# ArmazEthernet_-_Rev_A3.net
KiCad netlist of a schematic drawn in EAGLE
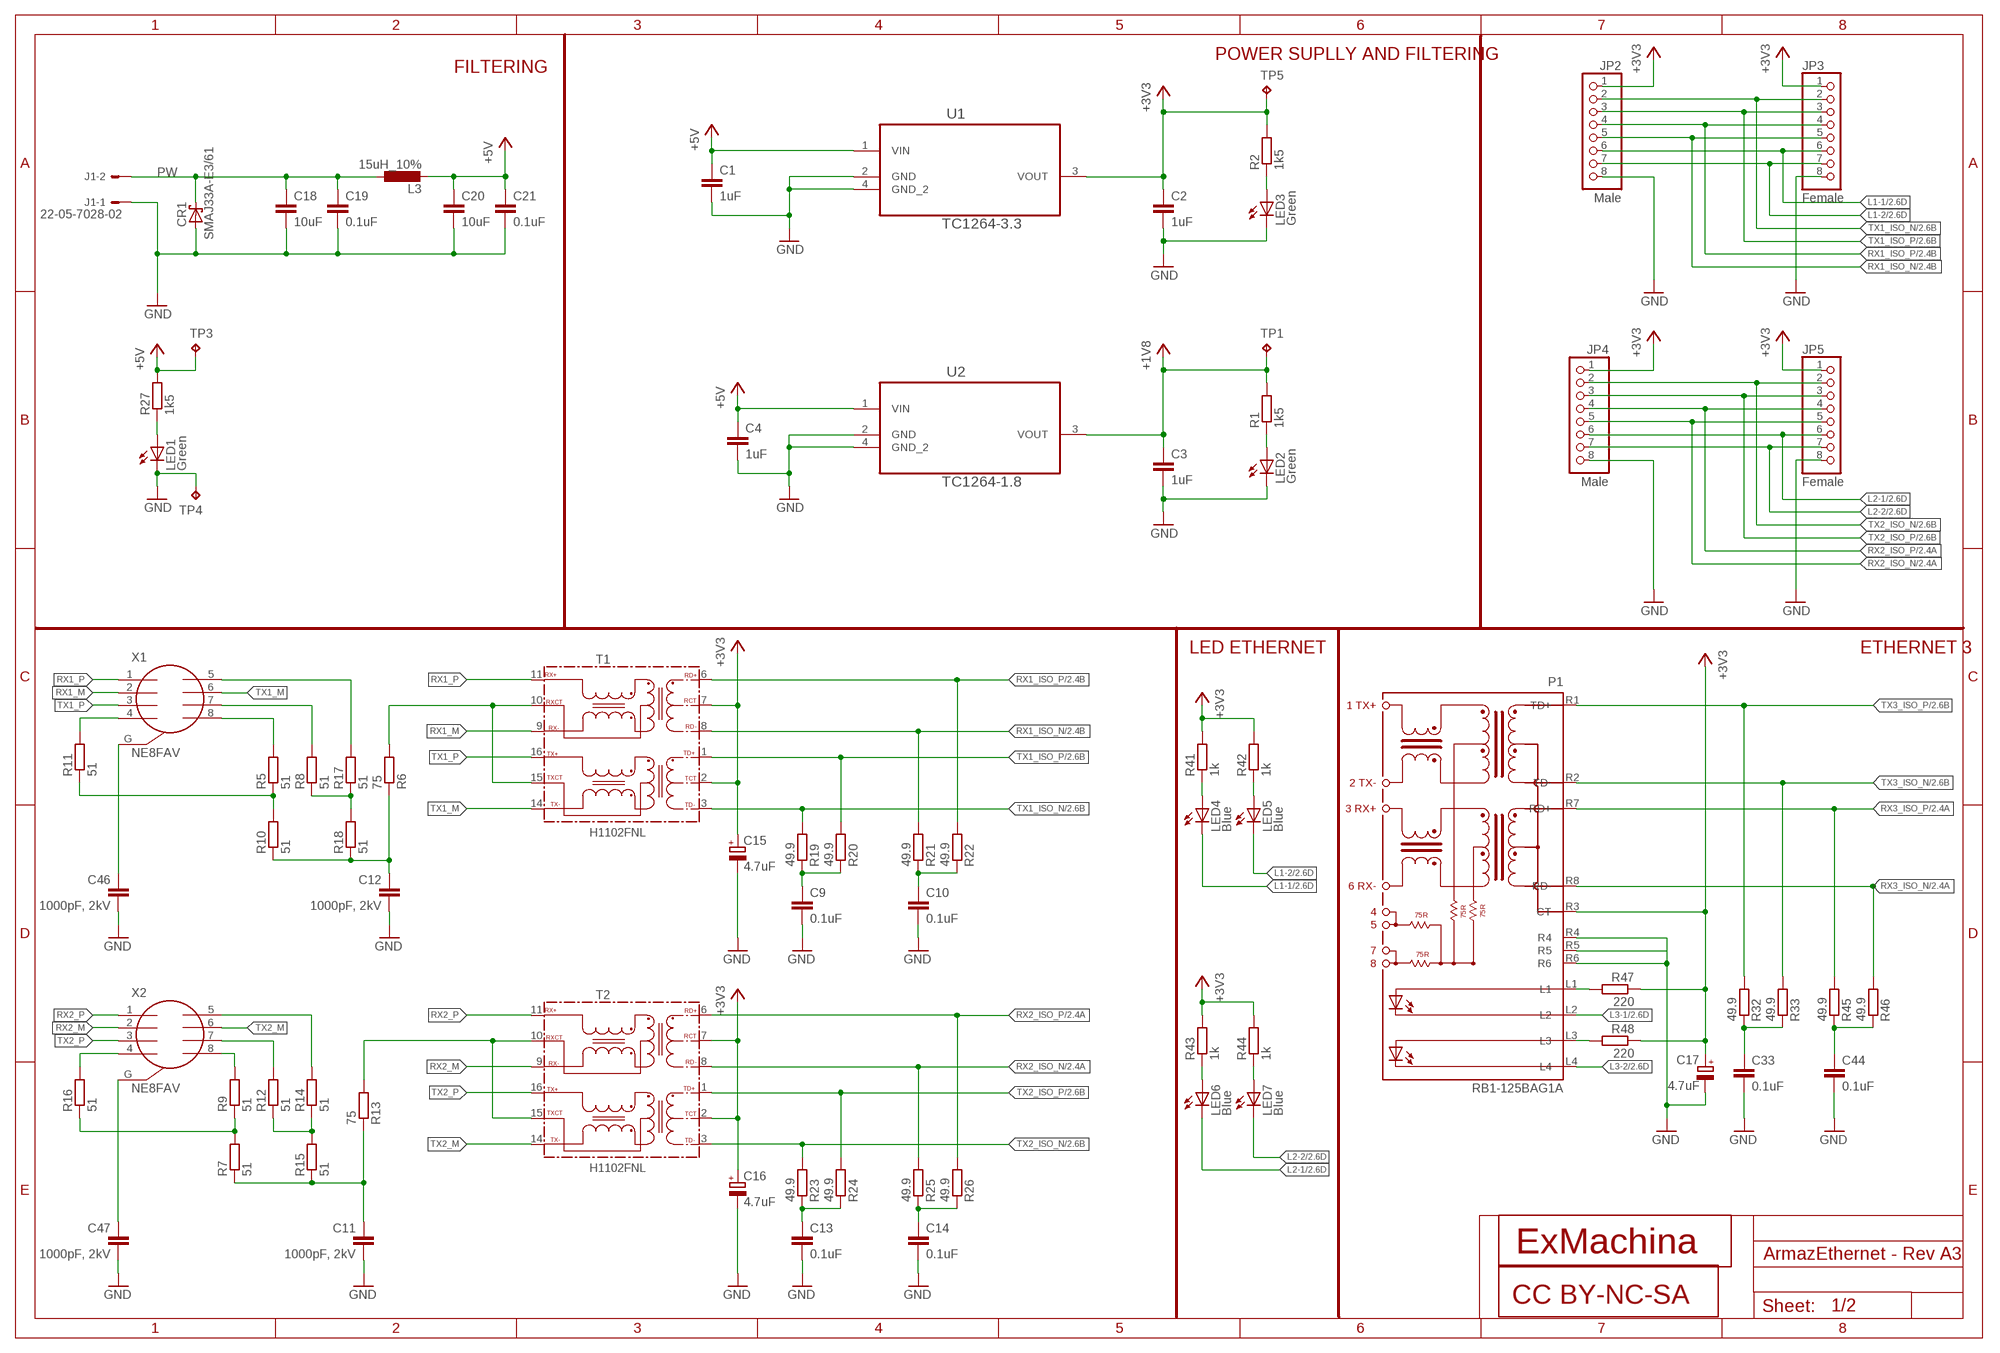
[diagram p0: schematic, sheet 1]
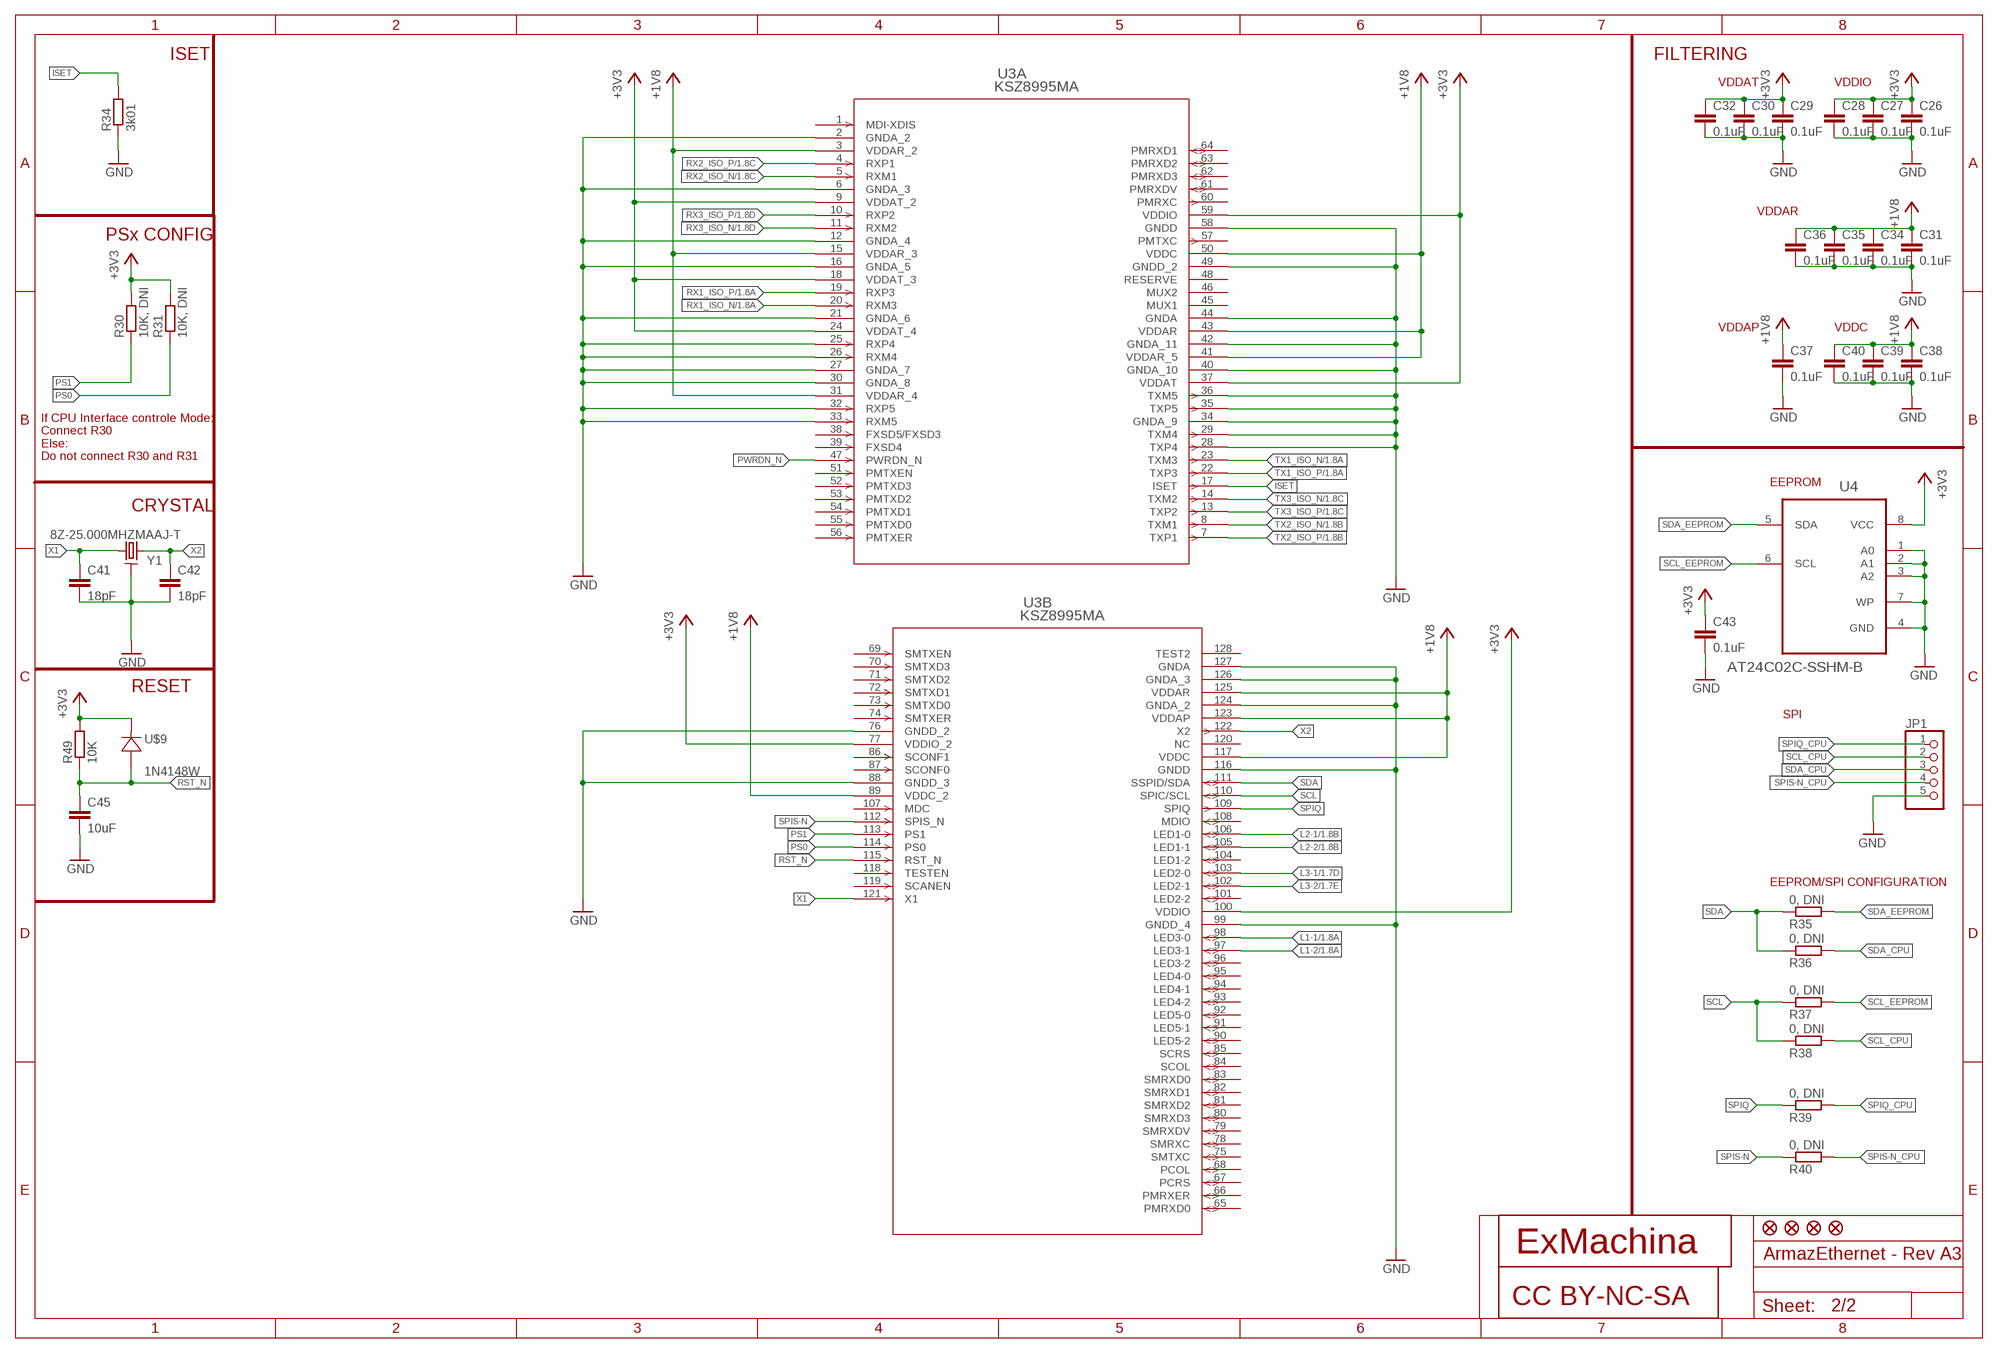
[diagram p1: schematic, sheet 2]

(export (version "E")
  (design (tool "Eeschema 10.0.6"))
  (components
    (comp (ref "C26")
      (value "0.1uF")
      (footprint "eagle-import:C0603")
      (fields (field (name "MF") "MULTICOMP") (field (name "MPN") "MC0603B104K250CT"))
      (libsource (lib "eagle-import") (part "C-EUC0603"))
    )
    (comp (ref "C27")
      (value "0.1uF")
      (footprint "eagle-import:C0603")
      (fields (field (name "MF") "MULTICOMP") (field (name "MPN") "MC0603B104K250CT"))
      (libsource (lib "eagle-import") (part "C-EUC0603"))
    )
    (comp (ref "C28")
      (value "0.1uF")
      (footprint "eagle-import:C0603")
      (fields (field (name "MF") "MULTICOMP") (field (name "MPN") "MC0603B104K250CT"))
      (libsource (lib "eagle-import") (part "C-EUC0603"))
    )
    (comp (ref "C29")
      (value "0.1uF")
      (footprint "eagle-import:C0603")
      (fields (field (name "MF") "MULTICOMP") (field (name "MPN") "MC0603B104K250CT"))
      (libsource (lib "eagle-import") (part "C-EUC0603"))
    )
    (comp (ref "C30")
      (value "0.1uF")
      (footprint "eagle-import:C0603")
      (fields (field (name "MF") "MULTICOMP") (field (name "MPN") "MC0603B104K250CT"))
      (libsource (lib "eagle-import") (part "C-EUC0603"))
    )
    (comp (ref "C31")
      (value "0.1uF")
      (footprint "eagle-import:C0603")
      (fields (field (name "MF") "MULTICOMP") (field (name "MPN") "MC0603B104K250CT"))
      (libsource (lib "eagle-import") (part "C-EUC0603"))
    )
    (comp (ref "C32")
      (value "0.1uF")
      (footprint "eagle-import:C0603")
      (fields (field (name "MF") "MULTICOMP") (field (name "MPN") "MC0603B104K250CT"))
      (libsource (lib "eagle-import") (part "C-EUC0603"))
    )
    (comp (ref "C34")
      (value "0.1uF")
      (footprint "eagle-import:C0603")
      (fields (field (name "MF") "MULTICOMP") (field (name "MPN") "MC0603B104K250CT"))
      (libsource (lib "eagle-import") (part "C-EUC0603"))
    )
    (comp (ref "C35")
      (value "0.1uF")
      (footprint "eagle-import:C0603")
      (fields (field (name "MF") "MULTICOMP") (field (name "MPN") "MC0603B104K250CT"))
      (libsource (lib "eagle-import") (part "C-EUC0603"))
    )
    (comp (ref "C36")
      (value "0.1uF")
      (footprint "eagle-import:C0603")
      (fields (field (name "MF") "MULTICOMP") (field (name "MPN") "MC0603B104K250CT"))
      (libsource (lib "eagle-import") (part "C-EUC0603"))
    )
    (comp (ref "C37")
      (value "0.1uF")
      (footprint "eagle-import:C0603")
      (fields (field (name "MF") "MULTICOMP") (field (name "MPN") "MC0603B104K250CT"))
      (libsource (lib "eagle-import") (part "C-EUC0603"))
    )
    (comp (ref "C38")
      (value "0.1uF")
      (footprint "eagle-import:C0603")
      (fields (field (name "MF") "MULTICOMP") (field (name "MPN") "MC0603B104K250CT"))
      (libsource (lib "eagle-import") (part "C-EUC0603"))
    )
    (comp (ref "C39")
      (value "0.1uF")
      (footprint "eagle-import:C0603")
      (fields (field (name "MF") "MULTICOMP") (field (name "MPN") "MC0603B104K250CT"))
      (libsource (lib "eagle-import") (part "C-EUC0603"))
    )
    (comp (ref "C40")
      (value "0.1uF")
      (footprint "eagle-import:C0603")
      (fields (field (name "MF") "MULTICOMP") (field (name "MPN") "MC0603B104K250CT"))
      (libsource (lib "eagle-import") (part "C-EUC0603"))
    )
    (comp (ref "C41")
      (value "18pF")
      (footprint "eagle-import:C0603")
      (fields (field (name "MF") "MULTICOMP") (field (name "MPN") "MC0603B183K160CT"))
      (libsource (lib "eagle-import") (part "C-EUC0603"))
    )
    (comp (ref "C42")
      (value "18pF")
      (footprint "eagle-import:C0603")
      (fields (field (name "MF") "MULTICOMP") (field (name "MPN") "MC0603B183K160CT"))
      (libsource (lib "eagle-import") (part "C-EUC0603"))
    )
    (comp (ref "C43")
      (value "0.1uF")
      (footprint "eagle-import:C0603")
      (fields (field (name "MF") "MULTICOMP") (field (name "MPN") "MC0603B104K250CT"))
      (libsource (lib "eagle-import") (part "C-EUC0603"))
    )
    (comp (ref "C45")
      (value "10uF")
      (footprint "eagle-import:C0603")
      (fields (field (name "MF") "MURATA") (field (name "MPN") "GRM32DR71C106KA01L"))
      (libsource (lib "eagle-import") (part "C-EUC0603"))
    )
    (comp (ref "JP1")
      (value "PINHD-1X5")
      (footprint "eagle-import:1X05")
      (libsource (lib "eagle-import") (part "PINHD-1X5"))
    )
    (comp (ref "JP7")
      (value "FIDUCIAL1X2")
      (footprint "eagle-import:FIDUCIAL-1X2")
      (libsource (lib "eagle-import") (part "FIDUCIAL1X2"))
    )
    (comp (ref "JP8")
      (value "FIDUCIAL1X2")
      (footprint "eagle-import:FIDUCIAL-1X2")
      (libsource (lib "eagle-import") (part "FIDUCIAL1X2"))
    )
    (comp (ref "JP9")
      (value "FIDUCIAL1X2")
      (footprint "eagle-import:FIDUCIAL-1X2")
      (libsource (lib "eagle-import") (part "FIDUCIAL1X2"))
    )
    (comp (ref "JP10")
      (value "FIDUCIAL1X2")
      (footprint "eagle-import:FIDUCIAL-1X2")
      (libsource (lib "eagle-import") (part "FIDUCIAL1X2"))
    )
    (comp (ref "R30")
      (value "10K, DNI")
      (footprint "eagle-import:R0603")
      (libsource (lib "eagle-import") (part "R-EU_R0603"))
    )
    (comp (ref "R31")
      (value "10K, DNI")
      (footprint "eagle-import:R0603")
      (libsource (lib "eagle-import") (part "R-EU_R0603"))
    )
    (comp (ref "R34")
      (value "3k01")
      (footprint "eagle-import:R0603")
      (fields (field (name "MF") "MULTICOMP") (field (name "MPN") "MCMR06X3001FTL"))
      (libsource (lib "eagle-import") (part "R-EU_R0603"))
    )
    (comp (ref "R35")
      (value "0, DNI")
      (footprint "eagle-import:R0603")
      (libsource (lib "eagle-import") (part "R-EU_R0603"))
    )
    (comp (ref "R36")
      (value "0, DNI")
      (footprint "eagle-import:R0603")
      (libsource (lib "eagle-import") (part "R-EU_R0603"))
    )
    (comp (ref "R37")
      (value "0, DNI")
      (footprint "eagle-import:R0603")
      (libsource (lib "eagle-import") (part "R-EU_R0603"))
    )
    (comp (ref "R38")
      (value "0, DNI")
      (footprint "eagle-import:R0603")
      (libsource (lib "eagle-import") (part "R-EU_R0603"))
    )
    (comp (ref "R39")
      (value "0, DNI")
      (footprint "eagle-import:R0603")
      (libsource (lib "eagle-import") (part "R-EU_R0603"))
    )
    (comp (ref "R40")
      (value "0, DNI")
      (footprint "eagle-import:R0603")
      (libsource (lib "eagle-import") (part "R-EU_R0603"))
    )
    (comp (ref "R49")
      (value "10K")
      (footprint "eagle-import:R0603")
      (fields (field (name "MF") "MULTICOMP") (field (name "MPN") "MCMR06X1002FTL"))
      (libsource (lib "eagle-import") (part "R-EU_R0603"))
    )
    (comp (ref "U$7")
      (value "CC-BY-NC-SA")
      (footprint "eagle-import:CC-BY-NC-SA")
      (libsource (lib "eagle-import") (part "CC-BY-NC-SA"))
    )
    (comp (ref "U$8")
      (value "EXMACHINA-LOGO-NAME")
      (footprint "eagle-import:EXM-LOGO-BASELINE")
      (libsource (lib "eagle-import") (part "EXMACHINA-LOGO-NAME"))
    )
    (comp (ref "U$9")
      (value "1N4148W")
      (footprint "eagle-import:SOD-123_MINI-SMA")
      (libsource (lib "eagle-import") (part "1N4148W"))
    )
    (comp (ref "U3")
      (value "KSZ8995MA")
      (footprint "eagle-import:PQFP-128_MQL")
      (fields
        (field (name "MANUFACTURER_PART_NUMBER") "ksz8995ma")
        (field (name "MF") "MICROCHIP")
        (field (name "MPN") "KSZ8995MA")
        (field (name "OC_FARNELL") "2509844")
        (field (name "OC_NEWARK") "70Y9044")
        (field (name "COPYRIGHT") "Copyright (C) 2015 Accelerated Designs. All rights reserved")
      )
      (libsource (lib "eagle-import") (part "KSZ8995MA"))
    )
    (comp (ref "U4")
      (value "AT24C02C-SSHM-B")
      (footprint "eagle-import:SOIC127P600X175-8N")
      (fields (field (name "MF") "ATMEL") (field (name "OC_FARNELL") "1971995"))
      (libsource (lib "eagle-import") (part "AT24C02C-SSHM-B"))
    )
    (comp (ref "Y1")
      (value "8Z-25.000MHZMAAJ-T")
      (footprint "eagle-import:SMD2.5X2")
      (fields (field (name "MF") "TXC") (field (name "MPN") "8Z-25.000MAAJ-T"))
      (libsource (lib "eagle-import") (part "8Z-25.000MHZMAAJ-T"))
    )
    (comp (ref "C1")
      (value "1uF")
      (footprint "eagle-import:C0603")
      (libsource (lib "eagle-import") (part "C-EUC0603"))
    )
    (comp (ref "C2")
      (value "1uF")
      (footprint "eagle-import:C0603")
      (libsource (lib "eagle-import") (part "C-EUC0603"))
    )
    (comp (ref "C3")
      (value "1uF")
      (footprint "eagle-import:C0603")
      (libsource (lib "eagle-import") (part "C-EUC0603"))
    )
    (comp (ref "C4")
      (value "1uF")
      (footprint "eagle-import:C0603")
      (libsource (lib "eagle-import") (part "C-EUC0603"))
    )
    (comp (ref "C9")
      (value "0.1uF")
      (footprint "eagle-import:C0603")
      (fields (field (name "MF") "MULTICOMP") (field (name "MPN") "MC0603B104K250CT"))
      (libsource (lib "eagle-import") (part "C-EUC0603"))
    )
    (comp (ref "C10")
      (value "0.1uF")
      (footprint "eagle-import:C0603")
      (fields (field (name "MF") "MULTICOMP") (field (name "MPN") "MC0603B104K250CT"))
      (libsource (lib "eagle-import") (part "C-EUC0603"))
    )
    (comp (ref "C11")
      (value "1000pF, 2kV")
      (footprint "eagle-import:C1206")
      (libsource (lib "eagle-import") (part "C-EUC1206"))
    )
    (comp (ref "C12")
      (value "1000pF, 2kV")
      (footprint "eagle-import:C1206")
      (libsource (lib "eagle-import") (part "C-EUC1206"))
    )
    (comp (ref "C13")
      (value "0.1uF")
      (footprint "eagle-import:C0603")
      (fields (field (name "MF") "MULTICOMP") (field (name "MPN") "MC0603B104K250CT"))
      (libsource (lib "eagle-import") (part "C-EUC0603"))
    )
    (comp (ref "C14")
      (value "0.1uF")
      (footprint "eagle-import:C0603")
      (fields (field (name "MF") "MULTICOMP") (field (name "MPN") "MC0603B104K250CT"))
      (libsource (lib "eagle-import") (part "C-EUC0603"))
    )
    (comp (ref "C15")
      (value "4.7uF")
      (footprint "eagle-import:CT3216")
      (libsource (lib "eagle-import") (part "CPOL-EUCT3216"))
    )
    (comp (ref "C16")
      (value "4.7uF")
      (footprint "eagle-import:CT3216")
      (libsource (lib "eagle-import") (part "CPOL-EUCT3216"))
    )
    (comp (ref "C17")
      (value "4.7uF")
      (footprint "eagle-import:CT3216")
      (libsource (lib "eagle-import") (part "CPOL-EUCT3216"))
    )
    (comp (ref "C18")
      (value "10uF")
      (footprint "eagle-import:C0603")
      (fields (field (name "MF") "MURATA") (field (name "MPN") "GRM32DR71C106KA01L"))
      (libsource (lib "eagle-import") (part "C-EUC0603"))
    )
    (comp (ref "C19")
      (value "0.1uF")
      (footprint "eagle-import:C0603")
      (fields (field (name "MF") "MULTICOMP") (field (name "MPN") "MC0603B104K250CT"))
      (libsource (lib "eagle-import") (part "C-EUC0603"))
    )
    (comp (ref "C20")
      (value "10uF")
      (footprint "eagle-import:C0603")
      (fields (field (name "MF") "MURATA") (field (name "MPN") "GRM32DR71C106KA01L"))
      (libsource (lib "eagle-import") (part "C-EUC0603"))
    )
    (comp (ref "C21")
      (value "0.1uF")
      (footprint "eagle-import:C0603")
      (fields (field (name "MF") "MULTICOMP") (field (name "MPN") "MC0603B104K250CT"))
      (libsource (lib "eagle-import") (part "C-EUC0603"))
    )
    (comp (ref "C33")
      (value "0.1uF")
      (footprint "eagle-import:C0603")
      (fields (field (name "MF") "MULTICOMP") (field (name "MPN") "MC0603B104K250CT"))
      (libsource (lib "eagle-import") (part "C-EUC0603"))
    )
    (comp (ref "C44")
      (value "0.1uF")
      (footprint "eagle-import:C0603")
      (fields (field (name "MF") "MULTICOMP") (field (name "MPN") "MC0603B104K250CT"))
      (libsource (lib "eagle-import") (part "C-EUC0603"))
    )
    (comp (ref "C46")
      (value "1000pF, 2kV")
      (footprint "eagle-import:C1206")
      (libsource (lib "eagle-import") (part "C-EUC1206"))
    )
    (comp (ref "C47")
      (value "1000pF, 2kV")
      (footprint "eagle-import:C1206")
      (libsource (lib "eagle-import") (part "C-EUC1206"))
    )
    (comp (ref "CR1")
      (value "SMAJ33A-E3/61")
      (footprint "eagle-import:DIODE_DO-214AC")
      (fields
        (field (name "RSPARTNUMBER") "7103462")
        (field (name "MF") "VISHAY")
        (field (name "MPN") "SMAJ33A-E3/5A")
        (field (name "COPYRIGHT") "Copyright (C) 2015 Accelerated Designs. All rights reserved")
      )
      (libsource (lib "eagle-import") (part "SMAJ33A-E3/61"))
    )
    (comp (ref "J1")
      (value "22-05-7028-02")
      (footprint "eagle-import:7395-02")
      (fields
        (field (name "MF") "MOLEX")
        (field (name "MPN") "22-05-7028")
        (field (name "OC_NEWARK") "25M1728")
      )
      (libsource (lib "eagle-import") (part "22-?-0205-7028"))
    )
    (comp (ref "JP2")
      (value "Male")
      (footprint "eagle-import:1X08")
      (fields (field (name "MF") "SAMTEC") (field (name "MPN") "TSW-108-15-T-S"))
      (libsource (lib "eagle-import") (part "PINHD-1X8"))
    )
    (comp (ref "JP3")
      (value "Female")
      (footprint "eagle-import:1X08")
      (fields (field (name "MF") "SAMTEC") (field (name "MPN") "SLW-108-01-T-S"))
      (libsource (lib "eagle-import") (part "PINHD-1X8"))
    )
    (comp (ref "JP4")
      (value "Male")
      (footprint "eagle-import:1X08")
      (fields (field (name "MF") "SAMTEC") (field (name "MPN") "TSW-108-15-T-S"))
      (libsource (lib "eagle-import") (part "PINHD-1X8"))
    )
    (comp (ref "JP5")
      (value "Female")
      (footprint "eagle-import:1X08")
      (fields (field (name "MF") "SAMTEC") (field (name "MPN") "SLW-108-01-T-S"))
      (libsource (lib "eagle-import") (part "PINHD-1X8"))
    )
    (comp (ref "L3")
      (value "15uH_10%")
      (footprint "eagle-import:L4532M")
      (libsource (lib "eagle-import") (part "L-EUL4532C"))
    )
    (comp (ref "LED1")
      (value "Green")
      (footprint "eagle-import:CHIP-LED0603")
      (fields (field (name "MF") "MULTICOMP") (field (name "MPN") "OVS-0604"))
      (libsource (lib "eagle-import") (part "LEDCHIP-LED0603"))
    )
    (comp (ref "LED2")
      (value "Green")
      (footprint "eagle-import:CHIP-LED0603")
      (fields (field (name "MF") "MULTICOMP") (field (name "MPN") "OVS-0604"))
      (libsource (lib "eagle-import") (part "LEDCHIP-LED0603"))
    )
    (comp (ref "LED3")
      (value "Green")
      (footprint "eagle-import:CHIP-LED0603")
      (fields (field (name "MF") "MULTICOMP") (field (name "MPN") "OVS-0604"))
      (libsource (lib "eagle-import") (part "LEDCHIP-LED0603"))
    )
    (comp (ref "LED4")
      (value "Blue")
      (footprint "eagle-import:CHIP-LED0603")
      (fields (field (name "MF") "MULTICOMP") (field (name "MPN") "OVS-0603"))
      (libsource (lib "eagle-import") (part "LEDCHIP-LED0603"))
    )
    (comp (ref "LED5")
      (value "Blue")
      (footprint "eagle-import:CHIP-LED0603")
      (fields (field (name "MF") "MULTICOMP") (field (name "MPN") "OVS-0603"))
      (libsource (lib "eagle-import") (part "LEDCHIP-LED0603"))
    )
    (comp (ref "LED6")
      (value "Blue")
      (footprint "eagle-import:CHIP-LED0603")
      (fields (field (name "MF") "MULTICOMP") (field (name "MPN") "OVS-0603"))
      (libsource (lib "eagle-import") (part "LEDCHIP-LED0603"))
    )
    (comp (ref "LED7")
      (value "Blue")
      (footprint "eagle-import:CHIP-LED0603")
      (fields (field (name "MF") "MULTICOMP") (field (name "MPN") "OVS-0603"))
      (libsource (lib "eagle-import") (part "LEDCHIP-LED0603"))
    )
    (comp (ref "P1")
      (value "RB1-125BAG1A")
      (footprint "eagle-import:WIZNET_RB1-125BAG1A")
      (libsource (lib "eagle-import") (part "RB1-125BAG1A"))
    )
    (comp (ref "R1")
      (value "1k5")
      (footprint "eagle-import:R0603")
      (fields (field (name "MF") "MULTICOMP") (field (name "MPN") "MCMR06X1501FTL"))
      (libsource (lib "eagle-import") (part "R-EU_R0603"))
    )
    (comp (ref "R2")
      (value "1k5")
      (footprint "eagle-import:R0603")
      (fields (field (name "MF") "MULTICOMP") (field (name "MPN") "MCMR06X1501FTL"))
      (libsource (lib "eagle-import") (part "R-EU_R0603"))
    )
    (comp (ref "R5")
      (value "51")
      (footprint "eagle-import:R0603")
      (fields (field (name "MF") "MULTICOMP") (field (name "MPN") "MCMR06X49R9FTL"))
      (libsource (lib "eagle-import") (part "R-EU_R0603"))
    )
    (comp (ref "R6")
      (value "75")
      (footprint "eagle-import:R0603")
      (fields (field (name "MF") "MULTICOMP") (field (name "MPN") "MCMR06X75R0FTL"))
      (libsource (lib "eagle-import") (part "R-EU_R0603"))
    )
    (comp (ref "R7")
      (value "51")
      (footprint "eagle-import:R0603")
      (fields (field (name "MF") "MULTICOMP") (field (name "MPN") "MCMR06X49R9FTL"))
      (libsource (lib "eagle-import") (part "R-EU_R0603"))
    )
    (comp (ref "R8")
      (value "51")
      (footprint "eagle-import:R0603")
      (fields (field (name "MF") "MULTICOMP") (field (name "MPN") "MCMR06X49R9FTL"))
      (libsource (lib "eagle-import") (part "R-EU_R0603"))
    )
    (comp (ref "R9")
      (value "51")
      (footprint "eagle-import:R0603")
      (fields (field (name "MF") "MULTICOMP") (field (name "MPN") "MCMR06X49R9FTL"))
      (libsource (lib "eagle-import") (part "R-EU_R0603"))
    )
    (comp (ref "R10")
      (value "51")
      (footprint "eagle-import:R0603")
      (fields (field (name "MF") "MULTICOMP") (field (name "MPN") "MCMR06X49R9FTL"))
      (libsource (lib "eagle-import") (part "R-EU_R0603"))
    )
    (comp (ref "R11")
      (value "51")
      (footprint "eagle-import:R0603")
      (fields (field (name "MF") "MULTICOMP") (field (name "MPN") "MCMR06X49R9FTL"))
      (libsource (lib "eagle-import") (part "R-EU_R0603"))
    )
    (comp (ref "R12")
      (value "51")
      (footprint "eagle-import:R0603")
      (fields (field (name "MF") "MULTICOMP") (field (name "MPN") "MCMR06X49R9FTL"))
      (libsource (lib "eagle-import") (part "R-EU_R0603"))
    )
    (comp (ref "R13")
      (value "75")
      (footprint "eagle-import:R0603")
      (fields (field (name "MF") "MULTICOMP") (field (name "MPN") "MCMR06X75R0FTL"))
      (libsource (lib "eagle-import") (part "R-EU_R0603"))
    )
    (comp (ref "R14")
      (value "51")
      (footprint "eagle-import:R0603")
      (fields (field (name "MF") "MULTICOMP") (field (name "MPN") "MCMR06X49R9FTL"))
      (libsource (lib "eagle-import") (part "R-EU_R0603"))
    )
    (comp (ref "R15")
      (value "51")
      (footprint "eagle-import:R0603")
      (fields (field (name "MF") "MULTICOMP") (field (name "MPN") "MCMR06X49R9FTL"))
      (libsource (lib "eagle-import") (part "R-EU_R0603"))
    )
    (comp (ref "R16")
      (value "51")
      (footprint "eagle-import:R0603")
      (fields (field (name "MF") "MULTICOMP") (field (name "MPN") "MCMR06X49R9FTL"))
      (libsource (lib "eagle-import") (part "R-EU_R0603"))
    )
    (comp (ref "R17")
      (value "51")
      (footprint "eagle-import:R0603")
      (fields (field (name "MF") "MULTICOMP") (field (name "MPN") "MCMR06X49R9FTL"))
      (libsource (lib "eagle-import") (part "R-EU_R0603"))
    )
    (comp (ref "R18")
      (value "51")
      (footprint "eagle-import:R0603")
      (fields (field (name "MF") "MULTICOMP") (field (name "MPN") "MCMR06X49R9FTL"))
      (libsource (lib "eagle-import") (part "R-EU_R0603"))
    )
    (comp (ref "R19")
      (value "49.9")
      (footprint "eagle-import:R0603")
      (fields (field (name "MF") "MULTICOMP") (field (name "MPN") "MCMR06X49R9FTL"))
      (libsource (lib "eagle-import") (part "R-EU_R0603"))
    )
    (comp (ref "R20")
      (value "49.9")
      (footprint "eagle-import:R0603")
      (fields (field (name "MF") "MULTICOMP") (field (name "MPN") "MCMR06X49R9FTL"))
      (libsource (lib "eagle-import") (part "R-EU_R0603"))
    )
    (comp (ref "R21")
      (value "49.9")
      (footprint "eagle-import:R0603")
      (fields (field (name "MF") "MULTICOMP") (field (name "MPN") "MCMR06X49R9FTL"))
      (libsource (lib "eagle-import") (part "R-EU_R0603"))
    )
    (comp (ref "R22")
      (value "49.9")
      (footprint "eagle-import:R0603")
      (fields (field (name "MF") "MULTICOMP") (field (name "MPN") "MCMR06X49R9FTL"))
      (libsource (lib "eagle-import") (part "R-EU_R0603"))
    )
    (comp (ref "R23")
      (value "49.9")
      (footprint "eagle-import:R0603")
      (fields (field (name "MF") "MULTICOMP") (field (name "MPN") "MCMR06X49R9FTL"))
      (libsource (lib "eagle-import") (part "R-EU_R0603"))
    )
    (comp (ref "R24")
      (value "49.9")
      (footprint "eagle-import:R0603")
      (fields (field (name "MF") "MULTICOMP") (field (name "MPN") "MCMR06X49R9FTL"))
      (libsource (lib "eagle-import") (part "R-EU_R0603"))
    )
    (comp (ref "R25")
      (value "49.9")
      (footprint "eagle-import:R0603")
      (fields (field (name "MF") "MULTICOMP") (field (name "MPN") "MCMR06X49R9FTL"))
      (libsource (lib "eagle-import") (part "R-EU_R0603"))
    )
    (comp (ref "R26")
      (value "49.9")
      (footprint "eagle-import:R0603")
      (fields (field (name "MF") "MULTICOMP") (field (name "MPN") "MCMR06X49R9FTL"))
      (libsource (lib "eagle-import") (part "R-EU_R0603"))
    )
    (comp (ref "R27")
      (value "1k5")
      (footprint "eagle-import:R0603")
      (fields (field (name "MF") "MULTICOMP") (field (name "MPN") "MCMR06X1501FTL"))
      (libsource (lib "eagle-import") (part "R-EU_R0603"))
    )
    (comp (ref "R32")
      (value "49.9")
      (footprint "eagle-import:R0603")
      (fields (field (name "MF") "MULTICOMP") (field (name "MPN") "MCMR06X49R9FTL"))
      (libsource (lib "eagle-import") (part "R-EU_R0603"))
    )
    (comp (ref "R33")
      (value "49.9")
      (footprint "eagle-import:R0603")
      (fields (field (name "MF") "MULTICOMP") (field (name "MPN") "MCMR06X49R9FTL"))
      (libsource (lib "eagle-import") (part "R-EU_R0603"))
    )
    (comp (ref "R41")
      (value "1k")
      (footprint "eagle-import:R0603")
      (fields (field (name "MF") "MULTICOMP") (field (name "MPN") "MCMR06X1001FTL"))
      (libsource (lib "eagle-import") (part "R-EU_R0603"))
    )
    (comp (ref "R42")
      (value "1k")
      (footprint "eagle-import:R0603")
      (fields (field (name "MF") "MULTICOMP") (field (name "MPN") "MCMR06X1001FTL"))
      (libsource (lib "eagle-import") (part "R-EU_R0603"))
    )
    (comp (ref "R43")
      (value "1k")
      (footprint "eagle-import:R0603")
      (fields (field (name "MF") "MULTICOMP") (field (name "MPN") "MCMR06X1001FTL"))
      (libsource (lib "eagle-import") (part "R-EU_R0603"))
    )
    (comp (ref "R44")
      (value "1k")
      (footprint "eagle-import:R0603")
      (fields (field (name "MF") "MULTICOMP") (field (name "MPN") "MCMR06X1001FTL"))
      (libsource (lib "eagle-import") (part "R-EU_R0603"))
    )
    (comp (ref "R45")
      (value "49.9")
      (footprint "eagle-import:R0603")
      (fields (field (name "MF") "MULTICOMP") (field (name "MPN") "MCMR06X49R9FTL"))
      (libsource (lib "eagle-import") (part "R-EU_R0603"))
    )
    (comp (ref "R46")
      (value "49.9")
      (footprint "eagle-import:R0603")
      (fields (field (name "MF") "MULTICOMP") (field (name "MPN") "MCMR06X49R9FTL"))
      (libsource (lib "eagle-import") (part "R-EU_R0603"))
    )
    (comp (ref "R47")
      (value "220")
      (footprint "eagle-import:R0603")
      (fields (field (name "MF") "MULTICOMP") (field (name "MPN") "MCMR06X2200FTL"))
      (libsource (lib "eagle-import") (part "R-EU_R0603"))
    )
    (comp (ref "R48")
      (value "220")
      (footprint "eagle-import:R0603")
      (fields (field (name "MF") "MULTICOMP") (field (name "MPN") "MCMR06X2200FTL"))
      (libsource (lib "eagle-import") (part "R-EU_R0603"))
    )
    (comp (ref "T1")
      (value "H1102FNL")
      (footprint "eagle-import:HXXXX")
      (libsource (lib "eagle-import") (part "H1102FNL"))
    )
    (comp (ref "T2")
      (value "H1102FNL")
      (footprint "eagle-import:HXXXX")
      (libsource (lib "eagle-import") (part "H1102FNL"))
    )
    (comp (ref "TP1")
      (value "TPB1,27")
      (footprint "eagle-import:B1,27")
      (libsource (lib "eagle-import") (part "TPB1,27"))
    )
    (comp (ref "TP3")
      (value "TPB1,27")
      (footprint "eagle-import:B1,27")
      (libsource (lib "eagle-import") (part "TPB1,27"))
    )
    (comp (ref "TP4")
      (value "TPB1,27")
      (footprint "eagle-import:B1,27")
      (libsource (lib "eagle-import") (part "TPB1,27"))
    )
    (comp (ref "TP5")
      (value "TPB1,27")
      (footprint "eagle-import:B1,27")
      (libsource (lib "eagle-import") (part "TPB1,27"))
    )
    (comp (ref "U$5")
      (value "EXMACHINA-LOGO-NAME")
      (footprint "eagle-import:EXM-LOGO-BASELINE")
      (libsource (lib "eagle-import") (part "EXMACHINA-LOGO-NAME"))
    )
    (comp (ref "U$6")
      (value "CC-BY-NC-SA")
      (footprint "eagle-import:CC-BY-NC-SA")
      (libsource (lib "eagle-import") (part "CC-BY-NC-SA"))
    )
    (comp (ref "U1")
      (value "TC1264-3.3")
      (footprint "eagle-import:SOT230P700X180-4N")
      (libsource (lib "eagle-import") (part "TC1264-3.3"))
    )
    (comp (ref "U2")
      (value "TC1264-1.8")
      (footprint "eagle-import:SOT230P700X180-4N")
      (libsource (lib "eagle-import") (part "TC1264-1.8"))
    )
    (comp (ref "X1")
      (value "NE8FAV")
      (footprint "eagle-import:NE8FAV")
      (fields (field (name "MF") "NEUTRIK") (field (name "OC_FARNELL") "1202031"))
      (libsource (lib "eagle-import") (part "NE8FAV"))
    )
    (comp (ref "X2")
      (value "NE8FAV")
      (footprint "eagle-import:NE8FAV")
      (fields (field (name "MF") "NEUTRIK") (field (name "OC_FARNELL") "1202031"))
      (libsource (lib "eagle-import") (part "NE8FAV"))
    )
  )
  (nets
    (net (code "1") (name "+1V8") (class "Default")
      (node (ref "C3") (pin "1") (pinfunction "1_1") (pintype "passive"))
      (node (ref "C31") (pin "1") (pinfunction "1_1") (pintype "passive"))
      (node (ref "C34") (pin "1") (pinfunction "1_1") (pintype "passive"))
      (node (ref "C35") (pin "1") (pinfunction "1_1") (pintype "passive"))
      (node (ref "C36") (pin "1") (pinfunction "1_1") (pintype "passive"))
      (node (ref "C37") (pin "1") (pinfunction "1_1") (pintype "passive"))
      (node (ref "C38") (pin "1") (pinfunction "1_1") (pintype "passive"))
      (node (ref "C39") (pin "1") (pinfunction "1_1") (pintype "passive"))
      (node (ref "C40") (pin "1") (pinfunction "1_1") (pintype "passive"))
      (node (ref "R1") (pin "2") (pinfunction "2_2") (pintype "passive"))
      (node (ref "TP1") (pin "TP") (pinfunction "TP_TP") (pintype "input"))
      (node (ref "U2") (pin "3") (pinfunction "VOUT_3") (pintype "output"))
      (node (ref "U3") (pin "117") (pinfunction "VDDC_117") (pintype "power_in"))
      (node (ref "U3") (pin "123") (pinfunction "VDDAP_123") (pintype "power_in"))
      (node (ref "U3") (pin "125") (pinfunction "VDDAR_125") (pintype "power_in"))
      (node (ref "U3") (pin "15") (pinfunction "VDDAR_3_15") (pintype "power_in"))
      (node (ref "U3") (pin "3") (pinfunction "VDDAR_2_3") (pintype "power_in"))
      (node (ref "U3") (pin "31") (pinfunction "VDDAR_4_31") (pintype "power_in"))
      (node (ref "U3") (pin "41") (pinfunction "VDDAR_5_41") (pintype "power_in"))
      (node (ref "U3") (pin "43") (pinfunction "VDDAR_43") (pintype "power_in"))
      (node (ref "U3") (pin "50") (pinfunction "VDDC_50") (pintype "power_in"))
      (node (ref "U3") (pin "89") (pinfunction "VDDC_2_89") (pintype "power_in"))
    )
    (net (code "2") (name "+3V3") (class "Default")
      (node (ref "C15") (pin "+") (pinfunction "+_+") (pintype "passive"))
      (node (ref "C16") (pin "+") (pinfunction "+_+") (pintype "passive"))
      (node (ref "C17") (pin "+") (pinfunction "+_+") (pintype "passive"))
      (node (ref "C2") (pin "1") (pinfunction "1_1") (pintype "passive"))
      (node (ref "C26") (pin "1") (pinfunction "1_1") (pintype "passive"))
      (node (ref "C27") (pin "1") (pinfunction "1_1") (pintype "passive"))
      (node (ref "C28") (pin "1") (pinfunction "1_1") (pintype "passive"))
      (node (ref "C29") (pin "1") (pinfunction "1_1") (pintype "passive"))
      (node (ref "C30") (pin "1") (pinfunction "1_1") (pintype "passive"))
      (node (ref "C32") (pin "1") (pinfunction "1_1") (pintype "passive"))
      (node (ref "C43") (pin "1") (pinfunction "1_1") (pintype "passive"))
      (node (ref "JP2") (pin "1") (pinfunction "1_1") (pintype "passive"))
      (node (ref "JP3") (pin "1") (pinfunction "1_1") (pintype "passive"))
      (node (ref "JP4") (pin "1") (pinfunction "1_1") (pintype "passive"))
      (node (ref "JP5") (pin "1") (pinfunction "1_1") (pintype "passive"))
      (node (ref "P1") (pin "R3") (pinfunction "CT_R3") (pintype "input"))
      (node (ref "R2") (pin "2") (pinfunction "2_2") (pintype "passive"))
      (node (ref "R30") (pin "2") (pinfunction "2_2") (pintype "passive"))
      (node (ref "R31") (pin "2") (pinfunction "2_2") (pintype "passive"))
      (node (ref "R41") (pin "2") (pinfunction "2_2") (pintype "passive"))
      (node (ref "R42") (pin "2") (pinfunction "2_2") (pintype "passive"))
      (node (ref "R43") (pin "2") (pinfunction "2_2") (pintype "passive"))
      (node (ref "R44") (pin "2") (pinfunction "2_2") (pintype "passive"))
      (node (ref "R47") (pin "1") (pinfunction "1_1") (pintype "passive"))
      (node (ref "R48") (pin "1") (pinfunction "1_1") (pintype "passive"))
      (node (ref "R49") (pin "2") (pinfunction "2_2") (pintype "passive"))
      (node (ref "T1") (pin "2") (pinfunction "TCT_2") (pintype "bidirectional"))
      (node (ref "T1") (pin "7") (pinfunction "RCT_7") (pintype "bidirectional"))
      (node (ref "T2") (pin "2") (pinfunction "TCT_2") (pintype "bidirectional"))
      (node (ref "T2") (pin "7") (pinfunction "RCT_7") (pintype "bidirectional"))
      (node (ref "TP5") (pin "TP") (pinfunction "TP_TP") (pintype "input"))
      (node (ref "U$9") (pin "C") (pinfunction "1_C") (pintype "passive"))
      (node (ref "U1") (pin "3") (pinfunction "VOUT_3") (pintype "output"))
      (node (ref "U3") (pin "100") (pinfunction "VDDIO_100") (pintype "power_in"))
      (node (ref "U3") (pin "18") (pinfunction "VDDAT_3_18") (pintype "power_in"))
      (node (ref "U3") (pin "24") (pinfunction "VDDAT_4_24") (pintype "power_in"))
      (node (ref "U3") (pin "37") (pinfunction "VDDAT_37") (pintype "power_in"))
      (node (ref "U3") (pin "59") (pinfunction "VDDIO_59") (pintype "power_in"))
      (node (ref "U3") (pin "77") (pinfunction "VDDIO_2_77") (pintype "power_in"))
      (node (ref "U3") (pin "9") (pinfunction "VDDAT_2_9") (pintype "power_in"))
      (node (ref "U4") (pin "8") (pinfunction "VCC_8") (pintype "power_in"))
    )
    (net (code "3") (name "+5V") (class "Default")
      (node (ref "C1") (pin "1") (pinfunction "1_1") (pintype "passive"))
      (node (ref "C20") (pin "1") (pinfunction "1_1") (pintype "passive"))
      (node (ref "C21") (pin "1") (pinfunction "1_1") (pintype "passive"))
      (node (ref "C4") (pin "1") (pinfunction "1_1") (pintype "passive"))
      (node (ref "L3") (pin "2") (pinfunction "2_2") (pintype "passive"))
      (node (ref "R27") (pin "2") (pinfunction "2_2") (pintype "passive"))
      (node (ref "TP3") (pin "TP") (pinfunction "TP_TP") (pintype "input"))
      (node (ref "U1") (pin "1") (pinfunction "VIN_1") (pintype "input"))
      (node (ref "U2") (pin "1") (pinfunction "VIN_1") (pintype "input"))
    )
    (net (code "4") (name "GND") (class "Default")
      (node (ref "C1") (pin "2") (pinfunction "2_2") (pintype "passive"))
      (node (ref "C10") (pin "2") (pinfunction "2_2") (pintype "passive"))
      (node (ref "C11") (pin "2") (pinfunction "2_2") (pintype "passive"))
      (node (ref "C12") (pin "2") (pinfunction "2_2") (pintype "passive"))
      (node (ref "C13") (pin "2") (pinfunction "2_2") (pintype "passive"))
      (node (ref "C14") (pin "2") (pinfunction "2_2") (pintype "passive"))
      (node (ref "C15") (pin "-") (pinfunction "-_-") (pintype "passive"))
      (node (ref "C16") (pin "-") (pinfunction "-_-") (pintype "passive"))
      (node (ref "C17") (pin "-") (pinfunction "-_-") (pintype "passive"))
      (node (ref "C18") (pin "2") (pinfunction "2_2") (pintype "passive"))
      (node (ref "C19") (pin "2") (pinfunction "2_2") (pintype "passive"))
      (node (ref "C2") (pin "2") (pinfunction "2_2") (pintype "passive"))
      (node (ref "C20") (pin "2") (pinfunction "2_2") (pintype "passive"))
      (node (ref "C21") (pin "2") (pinfunction "2_2") (pintype "passive"))
      (node (ref "C26") (pin "2") (pinfunction "2_2") (pintype "passive"))
      (node (ref "C27") (pin "2") (pinfunction "2_2") (pintype "passive"))
      (node (ref "C28") (pin "2") (pinfunction "2_2") (pintype "passive"))
      (node (ref "C29") (pin "2") (pinfunction "2_2") (pintype "passive"))
      (node (ref "C3") (pin "2") (pinfunction "2_2") (pintype "passive"))
      (node (ref "C30") (pin "2") (pinfunction "2_2") (pintype "passive"))
      (node (ref "C31") (pin "2") (pinfunction "2_2") (pintype "passive"))
      (node (ref "C32") (pin "2") (pinfunction "2_2") (pintype "passive"))
      (node (ref "C33") (pin "2") (pinfunction "2_2") (pintype "passive"))
      (node (ref "C34") (pin "2") (pinfunction "2_2") (pintype "passive"))
      (node (ref "C35") (pin "2") (pinfunction "2_2") (pintype "passive"))
      (node (ref "C36") (pin "2") (pinfunction "2_2") (pintype "passive"))
      (node (ref "C37") (pin "2") (pinfunction "2_2") (pintype "passive"))
      (node (ref "C38") (pin "2") (pinfunction "2_2") (pintype "passive"))
      (node (ref "C39") (pin "2") (pinfunction "2_2") (pintype "passive"))
      (node (ref "C4") (pin "2") (pinfunction "2_2") (pintype "passive"))
      (node (ref "C40") (pin "2") (pinfunction "2_2") (pintype "passive"))
      (node (ref "C41") (pin "2") (pinfunction "2_2") (pintype "passive"))
      (node (ref "C42") (pin "2") (pinfunction "2_2") (pintype "passive"))
      (node (ref "C43") (pin "2") (pinfunction "2_2") (pintype "passive"))
      (node (ref "C44") (pin "2") (pinfunction "2_2") (pintype "passive"))
      (node (ref "C45") (pin "2") (pinfunction "2_2") (pintype "passive"))
      (node (ref "C46") (pin "2") (pinfunction "2_2") (pintype "passive"))
      (node (ref "C47") (pin "2") (pinfunction "2_2") (pintype "passive"))
      (node (ref "C9") (pin "2") (pinfunction "2_2") (pintype "passive"))
      (node (ref "CR1") (pin "2") (pinfunction "A_2") (pintype "passive"))
      (node (ref "J1") (pin "1") (pinfunction "S_1") (pintype "passive"))
      (node (ref "JP1") (pin "5") (pinfunction "5_5") (pintype "passive"))
      (node (ref "JP2") (pin "8") (pinfunction "8_8") (pintype "passive"))
      (node (ref "JP3") (pin "8") (pinfunction "8_8") (pintype "passive"))
      (node (ref "JP4") (pin "8") (pinfunction "8_8") (pintype "passive"))
      (node (ref "JP5") (pin "8") (pinfunction "8_8") (pintype "passive"))
      (node (ref "LED1") (pin "C") (pinfunction "C_C") (pintype "passive"))
      (node (ref "LED2") (pin "C") (pinfunction "C_C") (pintype "passive"))
      (node (ref "LED3") (pin "C") (pinfunction "C_C") (pintype "passive"))
      (node (ref "P1") (pin "R4") (pinfunction "R4_R4") (pintype "input"))
      (node (ref "P1") (pin "R5") (pinfunction "R5_R5") (pintype "input"))
      (node (ref "P1") (pin "R6") (pinfunction "R6_R6") (pintype "input"))
      (node (ref "R34") (pin "1") (pinfunction "1_1") (pintype "passive"))
      (node (ref "TP4") (pin "TP") (pinfunction "TP_TP") (pintype "input"))
      (node (ref "U1") (pin "2") (pinfunction "GND_2") (pintype "passive"))
      (node (ref "U1") (pin "4") (pinfunction "GND_2_4") (pintype "passive"))
      (node (ref "U2") (pin "2") (pinfunction "GND_2") (pintype "passive"))
      (node (ref "U2") (pin "4") (pinfunction "GND_2_4") (pintype "passive"))
      (node (ref "U3") (pin "116") (pinfunction "GNDD_116") (pintype "power_in"))
      (node (ref "U3") (pin "12") (pinfunction "GNDA_4_12") (pintype "power_in"))
      (node (ref "U3") (pin "124") (pinfunction "GNDA_2_124") (pintype "power_in"))
      (node (ref "U3") (pin "126") (pinfunction "GNDA_3_126") (pintype "power_in"))
      (node (ref "U3") (pin "127") (pinfunction "GNDA_127") (pintype "power_in"))
      (node (ref "U3") (pin "16") (pinfunction "GNDA_5_16") (pintype "power_in"))
      (node (ref "U3") (pin "2") (pinfunction "GNDA_2_2") (pintype "power_in"))
      (node (ref "U3") (pin "21") (pinfunction "GNDA_6_21") (pintype "power_in"))
      (node (ref "U3") (pin "25") (pinfunction "RXP4_25") (pintype "input"))
      (node (ref "U3") (pin "26") (pinfunction "RXM4_26") (pintype "input"))
      (node (ref "U3") (pin "27") (pinfunction "GNDA_7_27") (pintype "power_in"))
      (node (ref "U3") (pin "28") (pinfunction "TXP4_28") (pintype "output"))
      (node (ref "U3") (pin "29") (pinfunction "TXM4_29") (pintype "output"))
      (node (ref "U3") (pin "30") (pinfunction "GNDA_8_30") (pintype "power_in"))
      (node (ref "U3") (pin "32") (pinfunction "RXP5_32") (pintype "input"))
      (node (ref "U3") (pin "33") (pinfunction "RXM5_33") (pintype "input"))
      (node (ref "U3") (pin "34") (pinfunction "GNDA_9_34") (pintype "power_in"))
      (node (ref "U3") (pin "35") (pinfunction "TXP5_35") (pintype "output"))
      (node (ref "U3") (pin "36") (pinfunction "TXM5_36") (pintype "output"))
      (node (ref "U3") (pin "40") (pinfunction "GNDA_10_40") (pintype "power_in"))
      (node (ref "U3") (pin "42") (pinfunction "GNDA_11_42") (pintype "power_in"))
      (node (ref "U3") (pin "44") (pinfunction "GNDA_44") (pintype "power_in"))
      (node (ref "U3") (pin "49") (pinfunction "GNDD_2_49") (pintype "passive"))
      (node (ref "U3") (pin "58") (pinfunction "GNDD_58") (pintype "power_in"))
      (node (ref "U3") (pin "6") (pinfunction "GNDA_3_6") (pintype "power_in"))
      (node (ref "U3") (pin "76") (pinfunction "GNDD_2_76") (pintype "power_in"))
      (node (ref "U3") (pin "88") (pinfunction "GNDD_3_88") (pintype "power_in"))
      (node (ref "U3") (pin "99") (pinfunction "GNDD_4_99") (pintype "power_in"))
      (node (ref "U4") (pin "1") (pinfunction "A0_1") (pintype "input"))
      (node (ref "U4") (pin "2") (pinfunction "A1_2") (pintype "input"))
      (node (ref "U4") (pin "3") (pinfunction "A2_3") (pintype "input"))
      (node (ref "U4") (pin "4") (pinfunction "GND_4") (pintype "power_in"))
      (node (ref "U4") (pin "7") (pinfunction "WP_7") (pintype "input"))
      (node (ref "Y1") (pin "2") (pinfunction "2_2") (pintype "passive"))
      (node (ref "Y1") (pin "4") (pinfunction "2_4") (pintype "passive"))
    )
    (net (code "5") (name "ISET") (class "Default")
      (node (ref "R34") (pin "2") (pinfunction "2_2") (pintype "passive"))
      (node (ref "U3") (pin "17") (pinfunction "ISET_17") (pintype "output"))
    )
    (net (code "6") (name "L1-1") (class "Default")
      (node (ref "JP2") (pin "6") (pinfunction "6_6") (pintype "passive"))
      (node (ref "JP3") (pin "6") (pinfunction "6_6") (pintype "passive"))
      (node (ref "LED4") (pin "C") (pinfunction "C_C") (pintype "passive"))
      (node (ref "U3") (pin "98") (pinfunction "LED3-0_98") (pintype "bidirectional"))
    )
    (net (code "7") (name "L1-2") (class "Default")
      (node (ref "JP2") (pin "7") (pinfunction "7_7") (pintype "passive"))
      (node (ref "JP3") (pin "7") (pinfunction "7_7") (pintype "passive"))
      (node (ref "LED5") (pin "C") (pinfunction "C_C") (pintype "passive"))
      (node (ref "U3") (pin "97") (pinfunction "LED3-1_97") (pintype "bidirectional"))
    )
    (net (code "8") (name "L2-1") (class "Default")
      (node (ref "JP4") (pin "6") (pinfunction "6_6") (pintype "passive"))
      (node (ref "JP5") (pin "6") (pinfunction "6_6") (pintype "passive"))
      (node (ref "LED6") (pin "C") (pinfunction "C_C") (pintype "passive"))
      (node (ref "U3") (pin "106") (pinfunction "LED1-0_106") (pintype "bidirectional"))
    )
    (net (code "9") (name "L2-2") (class "Default")
      (node (ref "JP4") (pin "7") (pinfunction "7_7") (pintype "passive"))
      (node (ref "JP5") (pin "7") (pinfunction "7_7") (pintype "passive"))
      (node (ref "LED7") (pin "C") (pinfunction "C_C") (pintype "passive"))
      (node (ref "U3") (pin "105") (pinfunction "LED1-1_105") (pintype "bidirectional"))
    )
    (net (code "10") (name "L3-1") (class "Default")
      (node (ref "P1") (pin "L2") (pinfunction "L2_L2") (pintype "passive"))
      (node (ref "U3") (pin "103") (pinfunction "LED2-0_103") (pintype "bidirectional"))
    )
    (net (code "11") (name "L3-2") (class "Default")
      (node (ref "P1") (pin "L4") (pinfunction "L4_L4") (pintype "passive"))
      (node (ref "U3") (pin "102") (pinfunction "LED2-1_102") (pintype "bidirectional"))
    )
    (net (code "12") (name "Net-(C9-Pad1)") (class "Default")
      (node (ref "C9") (pin "1") (pinfunction "1_1") (pintype "passive"))
      (node (ref "R19") (pin "1") (pinfunction "1_1") (pintype "passive"))
      (node (ref "R20") (pin "1") (pinfunction "1_1") (pintype "passive"))
    )
    (net (code "13") (name "Net-(C10-Pad1)") (class "Default")
      (node (ref "C10") (pin "1") (pinfunction "1_1") (pintype "passive"))
      (node (ref "R21") (pin "1") (pinfunction "1_1") (pintype "passive"))
      (node (ref "R22") (pin "1") (pinfunction "1_1") (pintype "passive"))
    )
    (net (code "14") (name "Net-(C11-Pad1)") (class "Default")
      (node (ref "C11") (pin "1") (pinfunction "1_1") (pintype "passive"))
      (node (ref "R13") (pin "1") (pinfunction "1_1") (pintype "passive"))
      (node (ref "R15") (pin "1") (pinfunction "1_1") (pintype "passive"))
      (node (ref "R7") (pin "1") (pinfunction "1_1") (pintype "passive"))
    )
    (net (code "15") (name "Net-(C12-Pad1)") (class "Default")
      (node (ref "C12") (pin "1") (pinfunction "1_1") (pintype "passive"))
      (node (ref "R10") (pin "1") (pinfunction "1_1") (pintype "passive"))
      (node (ref "R18") (pin "1") (pinfunction "1_1") (pintype "passive"))
      (node (ref "R6") (pin "1") (pinfunction "1_1") (pintype "passive"))
    )
    (net (code "16") (name "Net-(C13-Pad1)") (class "Default")
      (node (ref "C13") (pin "1") (pinfunction "1_1") (pintype "passive"))
      (node (ref "R23") (pin "1") (pinfunction "1_1") (pintype "passive"))
      (node (ref "R24") (pin "1") (pinfunction "1_1") (pintype "passive"))
    )
    (net (code "17") (name "Net-(C14-Pad1)") (class "Default")
      (node (ref "C14") (pin "1") (pinfunction "1_1") (pintype "passive"))
      (node (ref "R25") (pin "1") (pinfunction "1_1") (pintype "passive"))
      (node (ref "R26") (pin "1") (pinfunction "1_1") (pintype "passive"))
    )
    (net (code "18") (name "Net-(C33-Pad1)") (class "Default")
      (node (ref "C33") (pin "1") (pinfunction "1_1") (pintype "passive"))
      (node (ref "R32") (pin "1") (pinfunction "1_1") (pintype "passive"))
      (node (ref "R33") (pin "1") (pinfunction "1_1") (pintype "passive"))
    )
    (net (code "19") (name "Net-(C44-Pad1)") (class "Default")
      (node (ref "C44") (pin "1") (pinfunction "1_1") (pintype "passive"))
      (node (ref "R45") (pin "1") (pinfunction "1_1") (pintype "passive"))
      (node (ref "R46") (pin "1") (pinfunction "1_1") (pintype "passive"))
    )
    (net (code "20") (name "Net-(C46-Pad1)") (class "Default")
      (node (ref "C46") (pin "1") (pinfunction "1_1") (pintype "passive"))
      (node (ref "X1") (pin "G") (pinfunction "G_G") (pintype "passive"))
    )
    (net (code "21") (name "Net-(C47-Pad1)") (class "Default")
      (node (ref "C47") (pin "1") (pinfunction "1_1") (pintype "passive"))
      (node (ref "X2") (pin "G") (pinfunction "G_G") (pintype "passive"))
    )
    (net (code "22") (name "Net-(LED1-PadA)") (class "Default")
      (node (ref "LED1") (pin "A") (pinfunction "A_A") (pintype "passive"))
      (node (ref "R27") (pin "1") (pinfunction "1_1") (pintype "passive"))
    )
    (net (code "23") (name "Net-(LED2-PadA)") (class "Default")
      (node (ref "LED2") (pin "A") (pinfunction "A_A") (pintype "passive"))
      (node (ref "R1") (pin "1") (pinfunction "1_1") (pintype "passive"))
    )
    (net (code "24") (name "Net-(LED3-PadA)") (class "Default")
      (node (ref "LED3") (pin "A") (pinfunction "A_A") (pintype "passive"))
      (node (ref "R2") (pin "1") (pinfunction "1_1") (pintype "passive"))
    )
    (net (code "25") (name "Net-(LED4-PadA)") (class "Default")
      (node (ref "LED4") (pin "A") (pinfunction "A_A") (pintype "passive"))
      (node (ref "R41") (pin "1") (pinfunction "1_1") (pintype "passive"))
    )
    (net (code "26") (name "Net-(LED5-PadA)") (class "Default")
      (node (ref "LED5") (pin "A") (pinfunction "A_A") (pintype "passive"))
      (node (ref "R42") (pin "1") (pinfunction "1_1") (pintype "passive"))
    )
    (net (code "27") (name "Net-(LED6-PadA)") (class "Default")
      (node (ref "LED6") (pin "A") (pinfunction "A_A") (pintype "passive"))
      (node (ref "R43") (pin "1") (pinfunction "1_1") (pintype "passive"))
    )
    (net (code "28") (name "Net-(LED7-PadA)") (class "Default")
      (node (ref "LED7") (pin "A") (pinfunction "A_A") (pintype "passive"))
      (node (ref "R44") (pin "1") (pinfunction "1_1") (pintype "passive"))
    )
    (net (code "29") (name "Net-(P1-PadL1)") (class "Default")
      (node (ref "P1") (pin "L1") (pinfunction "L1_L1") (pintype "passive"))
      (node (ref "R47") (pin "2") (pinfunction "2_2") (pintype "passive"))
    )
    (net (code "30") (name "Net-(P1-PadL3)") (class "Default")
      (node (ref "P1") (pin "L3") (pinfunction "L3_L3") (pintype "passive"))
      (node (ref "R48") (pin "2") (pinfunction "2_2") (pintype "passive"))
    )
    (net (code "31") (name "Net-(R5-Pad2)") (class "Default")
      (node (ref "R5") (pin "2") (pinfunction "2_2") (pintype "passive"))
      (node (ref "X1") (pin "8") (pinfunction "8_8") (pintype "passive"))
    )
    (net (code "32") (name "Net-(R8-Pad2)") (class "Default")
      (node (ref "R8") (pin "2") (pinfunction "2_2") (pintype "passive"))
      (node (ref "X1") (pin "7") (pinfunction "7_7") (pintype "passive"))
    )
    (net (code "33") (name "Net-(R9-Pad2)") (class "Default")
      (node (ref "R9") (pin "2") (pinfunction "2_2") (pintype "passive"))
      (node (ref "X2") (pin "8") (pinfunction "8_8") (pintype "passive"))
    )
    (net (code "34") (name "Net-(R10-Pad2)") (class "Default")
      (node (ref "R10") (pin "2") (pinfunction "2_2") (pintype "passive"))
      (node (ref "R11") (pin "1") (pinfunction "1_1") (pintype "passive"))
      (node (ref "R5") (pin "1") (pinfunction "1_1") (pintype "passive"))
    )
    (net (code "35") (name "Net-(R11-Pad2)") (class "Default")
      (node (ref "R11") (pin "2") (pinfunction "2_2") (pintype "passive"))
      (node (ref "X1") (pin "4") (pinfunction "4_4") (pintype "passive"))
    )
    (net (code "36") (name "Net-(R12-Pad1)") (class "Default")
      (node (ref "R12") (pin "1") (pinfunction "1_1") (pintype "passive"))
      (node (ref "R14") (pin "1") (pinfunction "1_1") (pintype "passive"))
      (node (ref "R15") (pin "2") (pinfunction "2_2") (pintype "passive"))
    )
    (net (code "37") (name "Net-(R12-Pad2)") (class "Default")
      (node (ref "R12") (pin "2") (pinfunction "2_2") (pintype "passive"))
      (node (ref "X2") (pin "7") (pinfunction "7_7") (pintype "passive"))
    )
    (net (code "38") (name "Net-(R14-Pad2)") (class "Default")
      (node (ref "R14") (pin "2") (pinfunction "2_2") (pintype "passive"))
      (node (ref "X2") (pin "5") (pinfunction "5_5") (pintype "passive"))
    )
    (net (code "39") (name "Net-(R16-Pad1)") (class "Default")
      (node (ref "R16") (pin "1") (pinfunction "1_1") (pintype "passive"))
      (node (ref "R7") (pin "2") (pinfunction "2_2") (pintype "passive"))
      (node (ref "R9") (pin "1") (pinfunction "1_1") (pintype "passive"))
    )
    (net (code "40") (name "Net-(R16-Pad2)") (class "Default")
      (node (ref "R16") (pin "2") (pinfunction "2_2") (pintype "passive"))
      (node (ref "X2") (pin "4") (pinfunction "4_4") (pintype "passive"))
    )
    (net (code "41") (name "Net-(R17-Pad1)") (class "Default")
      (node (ref "R17") (pin "1") (pinfunction "1_1") (pintype "passive"))
      (node (ref "R18") (pin "2") (pinfunction "2_2") (pintype "passive"))
      (node (ref "R8") (pin "1") (pinfunction "1_1") (pintype "passive"))
    )
    (net (code "42") (name "Net-(R17-Pad2)") (class "Default")
      (node (ref "R17") (pin "2") (pinfunction "2_2") (pintype "passive"))
      (node (ref "X1") (pin "5") (pinfunction "5_5") (pintype "passive"))
    )
    (net (code "43") (name "Net-(T1-RXCT)") (class "Default")
      (node (ref "R6") (pin "2") (pinfunction "2_2") (pintype "passive"))
      (node (ref "T1") (pin "10") (pinfunction "RXCT_10") (pintype "bidirectional"))
      (node (ref "T1") (pin "15") (pinfunction "TXCT_15") (pintype "bidirectional"))
    )
    (net (code "44") (name "Net-(T2-RXCT)") (class "Default")
      (node (ref "R13") (pin "2") (pinfunction "2_2") (pintype "passive"))
      (node (ref "T2") (pin "10") (pinfunction "RXCT_10") (pintype "bidirectional"))
      (node (ref "T2") (pin "15") (pinfunction "TXCT_15") (pintype "bidirectional"))
    )
    (net (code "45") (name "PS0") (class "Default")
      (node (ref "R31") (pin "1") (pinfunction "1_1") (pintype "passive"))
      (node (ref "U3") (pin "114") (pinfunction "PS0_114") (pintype "input"))
    )
    (net (code "46") (name "PS1") (class "Default")
      (node (ref "R30") (pin "1") (pinfunction "1_1") (pintype "passive"))
      (node (ref "U3") (pin "113") (pinfunction "PS1_113") (pintype "input"))
    )
    (net (code "47") (name "PW") (class "Default")
      (node (ref "C18") (pin "1") (pinfunction "1_1") (pintype "passive"))
      (node (ref "C19") (pin "1") (pinfunction "1_1") (pintype "passive"))
      (node (ref "CR1") (pin "1") (pinfunction "C_1") (pintype "passive"))
      (node (ref "J1") (pin "2") (pinfunction "S_2") (pintype "passive"))
      (node (ref "L3") (pin "1") (pinfunction "1_1") (pintype "passive"))
    )
    (net (code "48") (name "PWRDN_N") (class "Default")
      (node (ref "U3") (pin "47") (pinfunction "PWRDN_N_47") (pintype "input"))
    )
    (net (code "49") (name "RST_N") (class "Default")
      (node (ref "C45") (pin "1") (pinfunction "1_1") (pintype "passive"))
      (node (ref "R49") (pin "1") (pinfunction "1_1") (pintype "passive"))
      (node (ref "U$9") (pin "A") (pinfunction "2_A") (pintype "passive"))
      (node (ref "U3") (pin "115") (pinfunction "RST_N_115") (pintype "input"))
    )
    (net (code "50") (name "RX1_ISO_N") (class "Default")
      (node (ref "JP2") (pin "5") (pinfunction "5_5") (pintype "passive"))
      (node (ref "JP3") (pin "5") (pinfunction "5_5") (pintype "passive"))
      (node (ref "R21") (pin "2") (pinfunction "2_2") (pintype "passive"))
      (node (ref "T1") (pin "8") (pinfunction "RD-_8") (pintype "bidirectional"))
      (node (ref "U3") (pin "20") (pinfunction "RXM3_20") (pintype "input"))
    )
    (net (code "51") (name "RX1_ISO_P") (class "Default")
      (node (ref "JP2") (pin "4") (pinfunction "4_4") (pintype "passive"))
      (node (ref "JP3") (pin "4") (pinfunction "4_4") (pintype "passive"))
      (node (ref "R22") (pin "2") (pinfunction "2_2") (pintype "passive"))
      (node (ref "T1") (pin "6") (pinfunction "RD+_6") (pintype "bidirectional"))
      (node (ref "U3") (pin "19") (pinfunction "RXP3_19") (pintype "input"))
    )
    (net (code "52") (name "RX1_M") (class "Default")
      (node (ref "T1") (pin "9") (pinfunction "RX-_9") (pintype "bidirectional"))
      (node (ref "X1") (pin "2") (pinfunction "2_2") (pintype "passive"))
    )
    (net (code "53") (name "RX1_P") (class "Default")
      (node (ref "T1") (pin "11") (pinfunction "RX+_11") (pintype "bidirectional"))
      (node (ref "X1") (pin "1") (pinfunction "1_1") (pintype "passive"))
    )
    (net (code "54") (name "RX2_ISO_N") (class "Default")
      (node (ref "JP4") (pin "5") (pinfunction "5_5") (pintype "passive"))
      (node (ref "JP5") (pin "5") (pinfunction "5_5") (pintype "passive"))
      (node (ref "R25") (pin "2") (pinfunction "2_2") (pintype "passive"))
      (node (ref "T2") (pin "8") (pinfunction "RD-_8") (pintype "bidirectional"))
      (node (ref "U3") (pin "5") (pinfunction "RXM1_5") (pintype "input"))
    )
    (net (code "55") (name "RX2_ISO_P") (class "Default")
      (node (ref "JP4") (pin "4") (pinfunction "4_4") (pintype "passive"))
      (node (ref "JP5") (pin "4") (pinfunction "4_4") (pintype "passive"))
      (node (ref "R26") (pin "2") (pinfunction "2_2") (pintype "passive"))
      (node (ref "T2") (pin "6") (pinfunction "RD+_6") (pintype "bidirectional"))
      (node (ref "U3") (pin "4") (pinfunction "RXP1_4") (pintype "input"))
    )
    (net (code "56") (name "RX2_M") (class "Default")
      (node (ref "T2") (pin "9") (pinfunction "RX-_9") (pintype "bidirectional"))
      (node (ref "X2") (pin "2") (pinfunction "2_2") (pintype "passive"))
    )
    (net (code "57") (name "RX2_P") (class "Default")
      (node (ref "T2") (pin "11") (pinfunction "RX+_11") (pintype "bidirectional"))
      (node (ref "X2") (pin "1") (pinfunction "1_1") (pintype "passive"))
    )
    (net (code "58") (name "RX3_ISO_N") (class "Default")
      (node (ref "P1") (pin "R8") (pinfunction "RD-_R8") (pintype "input"))
      (node (ref "R46") (pin "2") (pinfunction "2_2") (pintype "passive"))
      (node (ref "U3") (pin "11") (pinfunction "RXM2_11") (pintype "input"))
    )
    (net (code "59") (name "RX3_ISO_P") (class "Default")
      (node (ref "P1") (pin "R7") (pinfunction "RD+_R7") (pintype "input"))
      (node (ref "R45") (pin "2") (pinfunction "2_2") (pintype "passive"))
      (node (ref "U3") (pin "10") (pinfunction "RXP2_10") (pintype "input"))
    )
    (net (code "60") (name "SCL") (class "Default")
      (node (ref "R37") (pin "1") (pinfunction "1_1") (pintype "passive"))
      (node (ref "R38") (pin "1") (pinfunction "1_1") (pintype "passive"))
      (node (ref "U3") (pin "110") (pinfunction "SPIC/SCL_110") (pintype "bidirectional"))
    )
    (net (code "61") (name "SCL_CPU") (class "Default")
      (node (ref "JP1") (pin "2") (pinfunction "2_2") (pintype "passive"))
      (node (ref "R38") (pin "2") (pinfunction "2_2") (pintype "passive"))
    )
    (net (code "62") (name "SCL_EEPROM") (class "Default")
      (node (ref "R37") (pin "2") (pinfunction "2_2") (pintype "passive"))
      (node (ref "U4") (pin "6") (pinfunction "SCL_6") (pintype "input"))
    )
    (net (code "63") (name "SDA") (class "Default")
      (node (ref "R35") (pin "1") (pinfunction "1_1") (pintype "passive"))
      (node (ref "R36") (pin "1") (pinfunction "1_1") (pintype "passive"))
      (node (ref "U3") (pin "111") (pinfunction "SSPID/SDA_111") (pintype "bidirectional"))
    )
    (net (code "64") (name "SDA_CPU") (class "Default")
      (node (ref "JP1") (pin "3") (pinfunction "3_3") (pintype "passive"))
      (node (ref "R36") (pin "2") (pinfunction "2_2") (pintype "passive"))
    )
    (net (code "65") (name "SDA_EEPROM") (class "Default")
      (node (ref "R35") (pin "2") (pinfunction "2_2") (pintype "passive"))
      (node (ref "U4") (pin "5") (pinfunction "SDA_5") (pintype "bidirectional"))
    )
    (net (code "66") (name "SPIQ") (class "Default")
      (node (ref "R39") (pin "1") (pinfunction "1_1") (pintype "passive"))
      (node (ref "U3") (pin "109") (pinfunction "SPIQ_109") (pintype "output"))
    )
    (net (code "67") (name "SPIQ_CPU") (class "Default")
      (node (ref "JP1") (pin "1") (pinfunction "1_1") (pintype "passive"))
      (node (ref "R39") (pin "2") (pinfunction "2_2") (pintype "passive"))
    )
    (net (code "68") (name "SPIS-N") (class "Default")
      (node (ref "R40") (pin "1") (pinfunction "1_1") (pintype "passive"))
      (node (ref "U3") (pin "112") (pinfunction "SPIS_N_112") (pintype "input"))
    )
    (net (code "69") (name "SPIS-N_CPU") (class "Default")
      (node (ref "JP1") (pin "4") (pinfunction "4_4") (pintype "passive"))
      (node (ref "R40") (pin "2") (pinfunction "2_2") (pintype "passive"))
    )
    (net (code "70") (name "TX1_ISO_N") (class "Default")
      (node (ref "JP2") (pin "2") (pinfunction "2_2") (pintype "passive"))
      (node (ref "JP3") (pin "2") (pinfunction "2_2") (pintype "passive"))
      (node (ref "R19") (pin "2") (pinfunction "2_2") (pintype "passive"))
      (node (ref "T1") (pin "3") (pinfunction "TD-_3") (pintype "bidirectional"))
      (node (ref "U3") (pin "23") (pinfunction "TXM3_23") (pintype "output"))
    )
    (net (code "71") (name "TX1_ISO_P") (class "Default")
      (node (ref "JP2") (pin "3") (pinfunction "3_3") (pintype "passive"))
      (node (ref "JP3") (pin "3") (pinfunction "3_3") (pintype "passive"))
      (node (ref "R20") (pin "2") (pinfunction "2_2") (pintype "passive"))
      (node (ref "T1") (pin "1") (pinfunction "TD+_1") (pintype "bidirectional"))
      (node (ref "U3") (pin "22") (pinfunction "TXP3_22") (pintype "output"))
    )
    (net (code "72") (name "TX1_M") (class "Default")
      (node (ref "T1") (pin "14") (pinfunction "TX-_14") (pintype "bidirectional"))
      (node (ref "X1") (pin "6") (pinfunction "6_6") (pintype "passive"))
    )
    (net (code "73") (name "TX1_P") (class "Default")
      (node (ref "T1") (pin "16") (pinfunction "TX+_16") (pintype "bidirectional"))
      (node (ref "X1") (pin "3") (pinfunction "3_3") (pintype "passive"))
    )
    (net (code "74") (name "TX2_ISO_N") (class "Default")
      (node (ref "JP4") (pin "2") (pinfunction "2_2") (pintype "passive"))
      (node (ref "JP5") (pin "2") (pinfunction "2_2") (pintype "passive"))
      (node (ref "R23") (pin "2") (pinfunction "2_2") (pintype "passive"))
      (node (ref "T2") (pin "3") (pinfunction "TD-_3") (pintype "bidirectional"))
      (node (ref "U3") (pin "8") (pinfunction "TXM1_8") (pintype "output"))
    )
    (net (code "75") (name "TX2_ISO_P") (class "Default")
      (node (ref "JP4") (pin "3") (pinfunction "3_3") (pintype "passive"))
      (node (ref "JP5") (pin "3") (pinfunction "3_3") (pintype "passive"))
      (node (ref "R24") (pin "2") (pinfunction "2_2") (pintype "passive"))
      (node (ref "T2") (pin "1") (pinfunction "TD+_1") (pintype "bidirectional"))
      (node (ref "U3") (pin "7") (pinfunction "TXP1_7") (pintype "output"))
    )
    (net (code "76") (name "TX2_M") (class "Default")
      (node (ref "T2") (pin "14") (pinfunction "TX-_14") (pintype "bidirectional"))
      (node (ref "X2") (pin "6") (pinfunction "6_6") (pintype "passive"))
    )
    (net (code "77") (name "TX2_P") (class "Default")
      (node (ref "T2") (pin "16") (pinfunction "TX+_16") (pintype "bidirectional"))
      (node (ref "X2") (pin "3") (pinfunction "3_3") (pintype "passive"))
    )
    (net (code "78") (name "TX3_ISO_N") (class "Default")
      (node (ref "P1") (pin "R2") (pinfunction "TD-_R2") (pintype "input"))
      (node (ref "R33") (pin "2") (pinfunction "2_2") (pintype "passive"))
      (node (ref "U3") (pin "14") (pinfunction "TXM2_14") (pintype "output"))
    )
    (net (code "79") (name "TX3_ISO_P") (class "Default")
      (node (ref "P1") (pin "R1") (pinfunction "TD+_R1") (pintype "input"))
      (node (ref "R32") (pin "2") (pinfunction "2_2") (pintype "passive"))
      (node (ref "U3") (pin "13") (pinfunction "TXP2_13") (pintype "output"))
    )
    (net (code "80") (name "X1") (class "Default")
      (node (ref "C41") (pin "1") (pinfunction "1_1") (pintype "passive"))
      (node (ref "U3") (pin "121") (pinfunction "X1_121") (pintype "input"))
      (node (ref "Y1") (pin "1") (pinfunction "1_1") (pintype "passive"))
    )
    (net (code "81") (name "X2") (class "Default")
      (node (ref "C42") (pin "1") (pinfunction "1_1") (pintype "passive"))
      (node (ref "U3") (pin "122") (pinfunction "X2_122") (pintype "output"))
      (node (ref "Y1") (pin "3") (pinfunction "3_3") (pintype "passive"))
    )
    (net (code "82") (name "unconnected-(U3A-FXSD4-Pad39)") (class "Default")
      (node (ref "U3") (pin "39") (pinfunction "FXSD4_39") (pintype "input"))
    )
    (net (code "83") (name "unconnected-(U3A-FXSD5{slash}FXSD3-Pad38)") (class "Default")
      (node (ref "U3") (pin "38") (pinfunction "FXSD5/FXSD3_38") (pintype "input"))
    )
    (net (code "84") (name "unconnected-(U3A-MDI-XDIS-Pad1)") (class "Default")
      (node (ref "U3") (pin "1") (pinfunction "MDI-XDIS_1") (pintype "input"))
    )
    (net (code "85") (name "unconnected-(U3A-MUX1-Pad45)") (class "Default")
      (node (ref "U3") (pin "45") (pinfunction "MUX1_45") (pintype "passive"))
    )
    (net (code "86") (name "unconnected-(U3A-MUX2-Pad46)") (class "Default")
      (node (ref "U3") (pin "46") (pinfunction "MUX2_46") (pintype "passive"))
    )
    (net (code "87") (name "unconnected-(U3A-PMRXC-Pad60)") (class "Default")
      (node (ref "U3") (pin "60") (pinfunction "PMRXC_60") (pintype "output"))
    )
    (net (code "88") (name "unconnected-(U3A-PMRXD1-Pad64)") (class "Default")
      (node (ref "U3") (pin "64") (pinfunction "PMRXD1_64") (pintype "bidirectional"))
    )
    (net (code "89") (name "unconnected-(U3A-PMRXD2-Pad63)") (class "Default")
      (node (ref "U3") (pin "63") (pinfunction "PMRXD2_63") (pintype "bidirectional"))
    )
    (net (code "90") (name "unconnected-(U3A-PMRXD3-Pad62)") (class "Default")
      (node (ref "U3") (pin "62") (pinfunction "PMRXD3_62") (pintype "bidirectional"))
    )
    (net (code "91") (name "unconnected-(U3A-PMRXDV-Pad61)") (class "Default")
      (node (ref "U3") (pin "61") (pinfunction "PMRXDV_61") (pintype "bidirectional"))
    )
    (net (code "92") (name "unconnected-(U3A-PMTXC-Pad57)") (class "Default")
      (node (ref "U3") (pin "57") (pinfunction "PMTXC_57") (pintype "output"))
    )
    (net (code "93") (name "unconnected-(U3A-PMTXD0-Pad55)") (class "Default")
      (node (ref "U3") (pin "55") (pinfunction "PMTXD0_55") (pintype "input"))
    )
    (net (code "94") (name "unconnected-(U3A-PMTXD1-Pad54)") (class "Default")
      (node (ref "U3") (pin "54") (pinfunction "PMTXD1_54") (pintype "input"))
    )
    (net (code "95") (name "unconnected-(U3A-PMTXD2-Pad53)") (class "Default")
      (node (ref "U3") (pin "53") (pinfunction "PMTXD2_53") (pintype "input"))
    )
    (net (code "96") (name "unconnected-(U3A-PMTXD3-Pad52)") (class "Default")
      (node (ref "U3") (pin "52") (pinfunction "PMTXD3_52") (pintype "input"))
    )
    (net (code "97") (name "unconnected-(U3A-PMTXEN-Pad51)") (class "Default")
      (node (ref "U3") (pin "51") (pinfunction "PMTXEN_51") (pintype "input"))
    )
    (net (code "98") (name "unconnected-(U3A-PMTXER-Pad56)") (class "Default")
      (node (ref "U3") (pin "56") (pinfunction "PMTXER_56") (pintype "input"))
    )
    (net (code "99") (name "unconnected-(U3A-RESERVE-Pad48)") (class "Default")
      (node (ref "U3") (pin "48") (pinfunction "RESERVE_48") (pintype "passive"))
    )
    (net (code "100") (name "unconnected-(U3B-LED1-2-Pad104)") (class "Default")
      (node (ref "U3") (pin "104") (pinfunction "LED1-2_104") (pintype "bidirectional"))
    )
    (net (code "101") (name "unconnected-(U3B-LED2-2-Pad101)") (class "Default")
      (node (ref "U3") (pin "101") (pinfunction "LED2-2_101") (pintype "bidirectional"))
    )
    (net (code "102") (name "unconnected-(U3B-LED3-2-Pad96)") (class "Default")
      (node (ref "U3") (pin "96") (pinfunction "LED3-2_96") (pintype "bidirectional"))
    )
    (net (code "103") (name "unconnected-(U3B-LED4-0-Pad95)") (class "Default")
      (node (ref "U3") (pin "95") (pinfunction "LED4-0_95") (pintype "bidirectional"))
    )
    (net (code "104") (name "unconnected-(U3B-LED4-1-Pad94)") (class "Default")
      (node (ref "U3") (pin "94") (pinfunction "LED4-1_94") (pintype "bidirectional"))
    )
    (net (code "105") (name "unconnected-(U3B-LED4-2-Pad93)") (class "Default")
      (node (ref "U3") (pin "93") (pinfunction "LED4-2_93") (pintype "bidirectional"))
    )
    (net (code "106") (name "unconnected-(U3B-LED5-0-Pad92)") (class "Default")
      (node (ref "U3") (pin "92") (pinfunction "LED5-0_92") (pintype "bidirectional"))
    )
    (net (code "107") (name "unconnected-(U3B-LED5-1-Pad91)") (class "Default")
      (node (ref "U3") (pin "91") (pinfunction "LED5-1_91") (pintype "bidirectional"))
    )
    (net (code "108") (name "unconnected-(U3B-LED5-2-Pad90)") (class "Default")
      (node (ref "U3") (pin "90") (pinfunction "LED5-2_90") (pintype "bidirectional"))
    )
    (net (code "109") (name "unconnected-(U3B-MDC-Pad107)") (class "Default")
      (node (ref "U3") (pin "107") (pinfunction "MDC_107") (pintype "input"))
    )
    (net (code "110") (name "unconnected-(U3B-MDIO-Pad108)") (class "Default")
      (node (ref "U3") (pin "108") (pinfunction "MDIO_108") (pintype "bidirectional"))
    )
    (net (code "111") (name "unconnected-(U3B-NC-Pad120)") (class "Default")
      (node (ref "U3") (pin "120") (pinfunction "NC_120") (pintype "no_connect"))
    )
    (net (code "112") (name "unconnected-(U3B-PCOL-Pad68)") (class "Default")
      (node (ref "U3") (pin "68") (pinfunction "PCOL_68") (pintype "bidirectional"))
    )
    (net (code "113") (name "unconnected-(U3B-PCRS-Pad67)") (class "Default")
      (node (ref "U3") (pin "67") (pinfunction "PCRS_67") (pintype "bidirectional"))
    )
    (net (code "114") (name "unconnected-(U3B-PMRXD0-Pad65)") (class "Default")
      (node (ref "U3") (pin "65") (pinfunction "PMRXD0_65") (pintype "bidirectional"))
    )
    (net (code "115") (name "unconnected-(U3B-PMRXER-Pad66)") (class "Default")
      (node (ref "U3") (pin "66") (pinfunction "PMRXER_66") (pintype "bidirectional"))
    )
    (net (code "116") (name "unconnected-(U3B-SCANEN-Pad119)") (class "Default")
      (node (ref "U3") (pin "119") (pinfunction "SCANEN_119") (pintype "input"))
    )
    (net (code "117") (name "unconnected-(U3B-SCOL-Pad84)") (class "Default")
      (node (ref "U3") (pin "84") (pinfunction "SCOL_84") (pintype "bidirectional"))
    )
    (net (code "118") (name "unconnected-(U3B-SCONF0-Pad87)") (class "Default")
      (node (ref "U3") (pin "87") (pinfunction "SCONF0_87") (pintype "input"))
    )
    (net (code "119") (name "unconnected-(U3B-SCONF1-Pad86)") (class "Default")
      (node (ref "U3") (pin "86") (pinfunction "SCONF1_86") (pintype "input"))
    )
    (net (code "120") (name "unconnected-(U3B-SCRS-Pad85)") (class "Default")
      (node (ref "U3") (pin "85") (pinfunction "SCRS_85") (pintype "bidirectional"))
    )
    (net (code "121") (name "unconnected-(U3B-SMRXC-Pad78)") (class "Default")
      (node (ref "U3") (pin "78") (pinfunction "SMRXC_78") (pintype "bidirectional"))
    )
    (net (code "122") (name "unconnected-(U3B-SMRXD0-Pad83)") (class "Default")
      (node (ref "U3") (pin "83") (pinfunction "SMRXD0_83") (pintype "bidirectional"))
    )
    (net (code "123") (name "unconnected-(U3B-SMRXD1-Pad82)") (class "Default")
      (node (ref "U3") (pin "82") (pinfunction "SMRXD1_82") (pintype "bidirectional"))
    )
    (net (code "124") (name "unconnected-(U3B-SMRXD2-Pad81)") (class "Default")
      (node (ref "U3") (pin "81") (pinfunction "SMRXD2_81") (pintype "bidirectional"))
    )
    (net (code "125") (name "unconnected-(U3B-SMRXD3-Pad80)") (class "Default")
      (node (ref "U3") (pin "80") (pinfunction "SMRXD3_80") (pintype "bidirectional"))
    )
    (net (code "126") (name "unconnected-(U3B-SMRXDV-Pad79)") (class "Default")
      (node (ref "U3") (pin "79") (pinfunction "SMRXDV_79") (pintype "bidirectional"))
    )
    (net (code "127") (name "unconnected-(U3B-SMTXC-Pad75)") (class "Default")
      (node (ref "U3") (pin "75") (pinfunction "SMTXC_75") (pintype "bidirectional"))
    )
    (net (code "128") (name "unconnected-(U3B-SMTXD0-Pad73)") (class "Default")
      (node (ref "U3") (pin "73") (pinfunction "SMTXD0_73") (pintype "input"))
    )
    (net (code "129") (name "unconnected-(U3B-SMTXD1-Pad72)") (class "Default")
      (node (ref "U3") (pin "72") (pinfunction "SMTXD1_72") (pintype "input"))
    )
    (net (code "130") (name "unconnected-(U3B-SMTXD2-Pad71)") (class "Default")
      (node (ref "U3") (pin "71") (pinfunction "SMTXD2_71") (pintype "input"))
    )
    (net (code "131") (name "unconnected-(U3B-SMTXD3-Pad70)") (class "Default")
      (node (ref "U3") (pin "70") (pinfunction "SMTXD3_70") (pintype "input"))
    )
    (net (code "132") (name "unconnected-(U3B-SMTXEN-Pad69)") (class "Default")
      (node (ref "U3") (pin "69") (pinfunction "SMTXEN_69") (pintype "input"))
    )
    (net (code "133") (name "unconnected-(U3B-SMTXER-Pad74)") (class "Default")
      (node (ref "U3") (pin "74") (pinfunction "SMTXER_74") (pintype "input"))
    )
    (net (code "134") (name "unconnected-(U3B-TEST2-Pad128)") (class "Default")
      (node (ref "U3") (pin "128") (pinfunction "TEST2_128") (pintype "passive"))
    )
    (net (code "135") (name "unconnected-(U3B-TESTEN-Pad118)") (class "Default")
      (node (ref "U3") (pin "118") (pinfunction "TESTEN_118") (pintype "input"))
    )
  )
)
